# LM5116.net
KiCad netlist of a schematic drawn in EAGLE
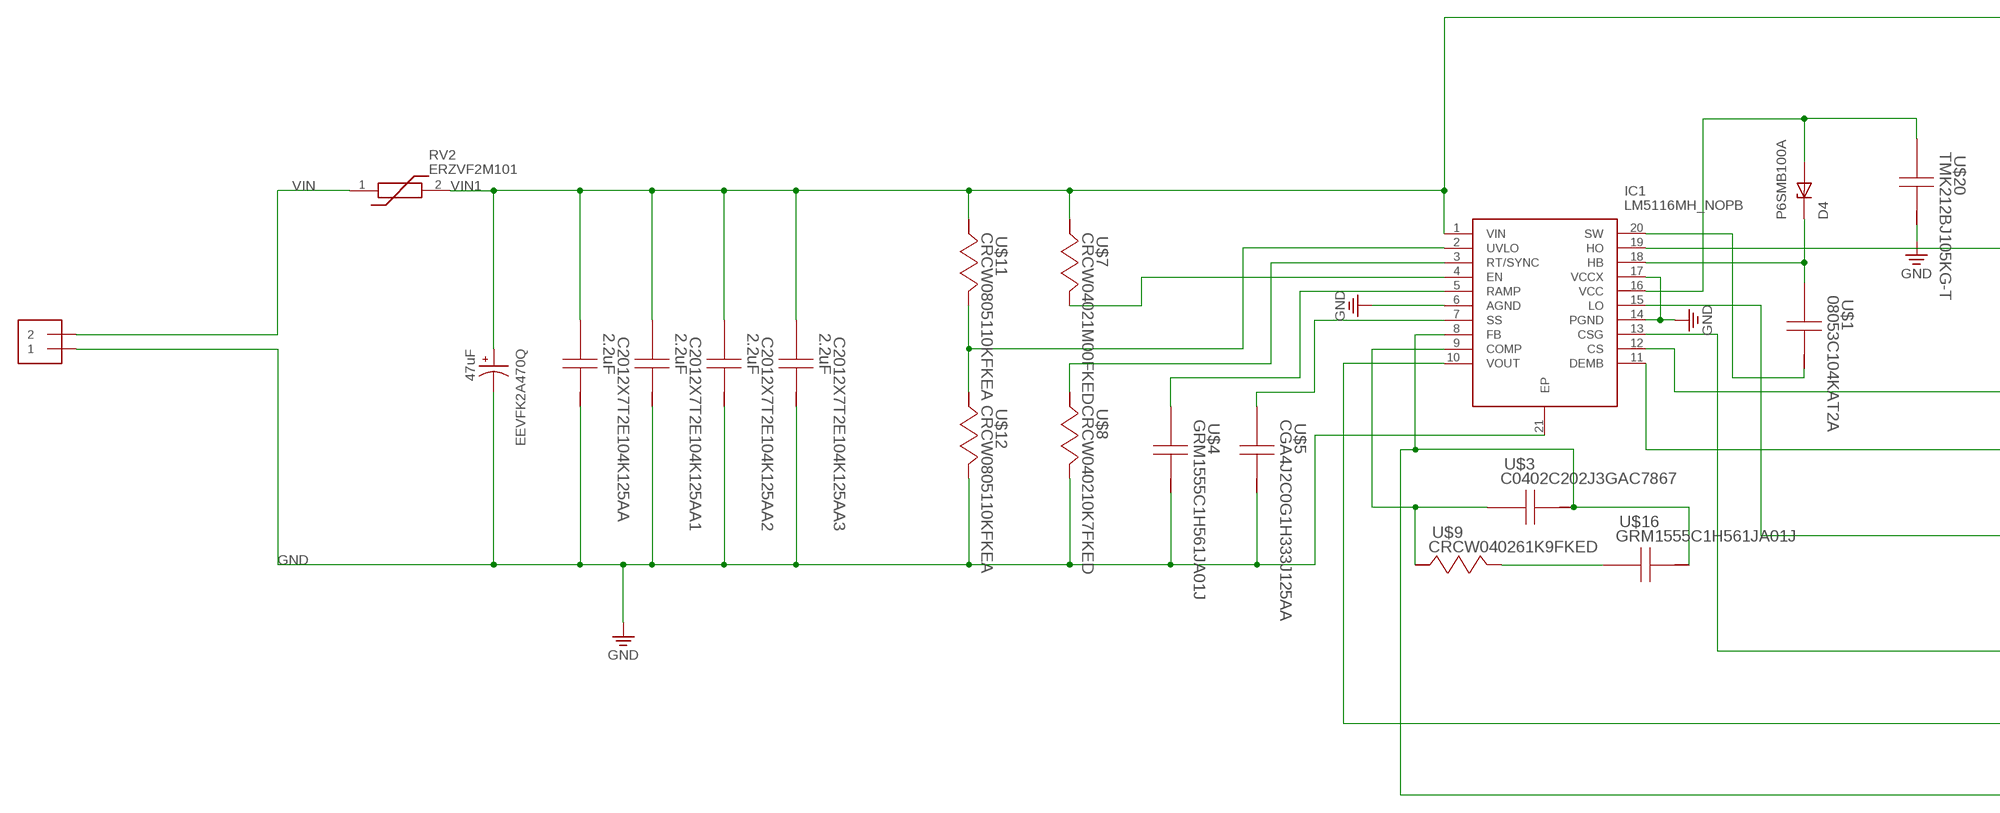
[diagram p0: schematic, sheet 1, part 1 of 2]
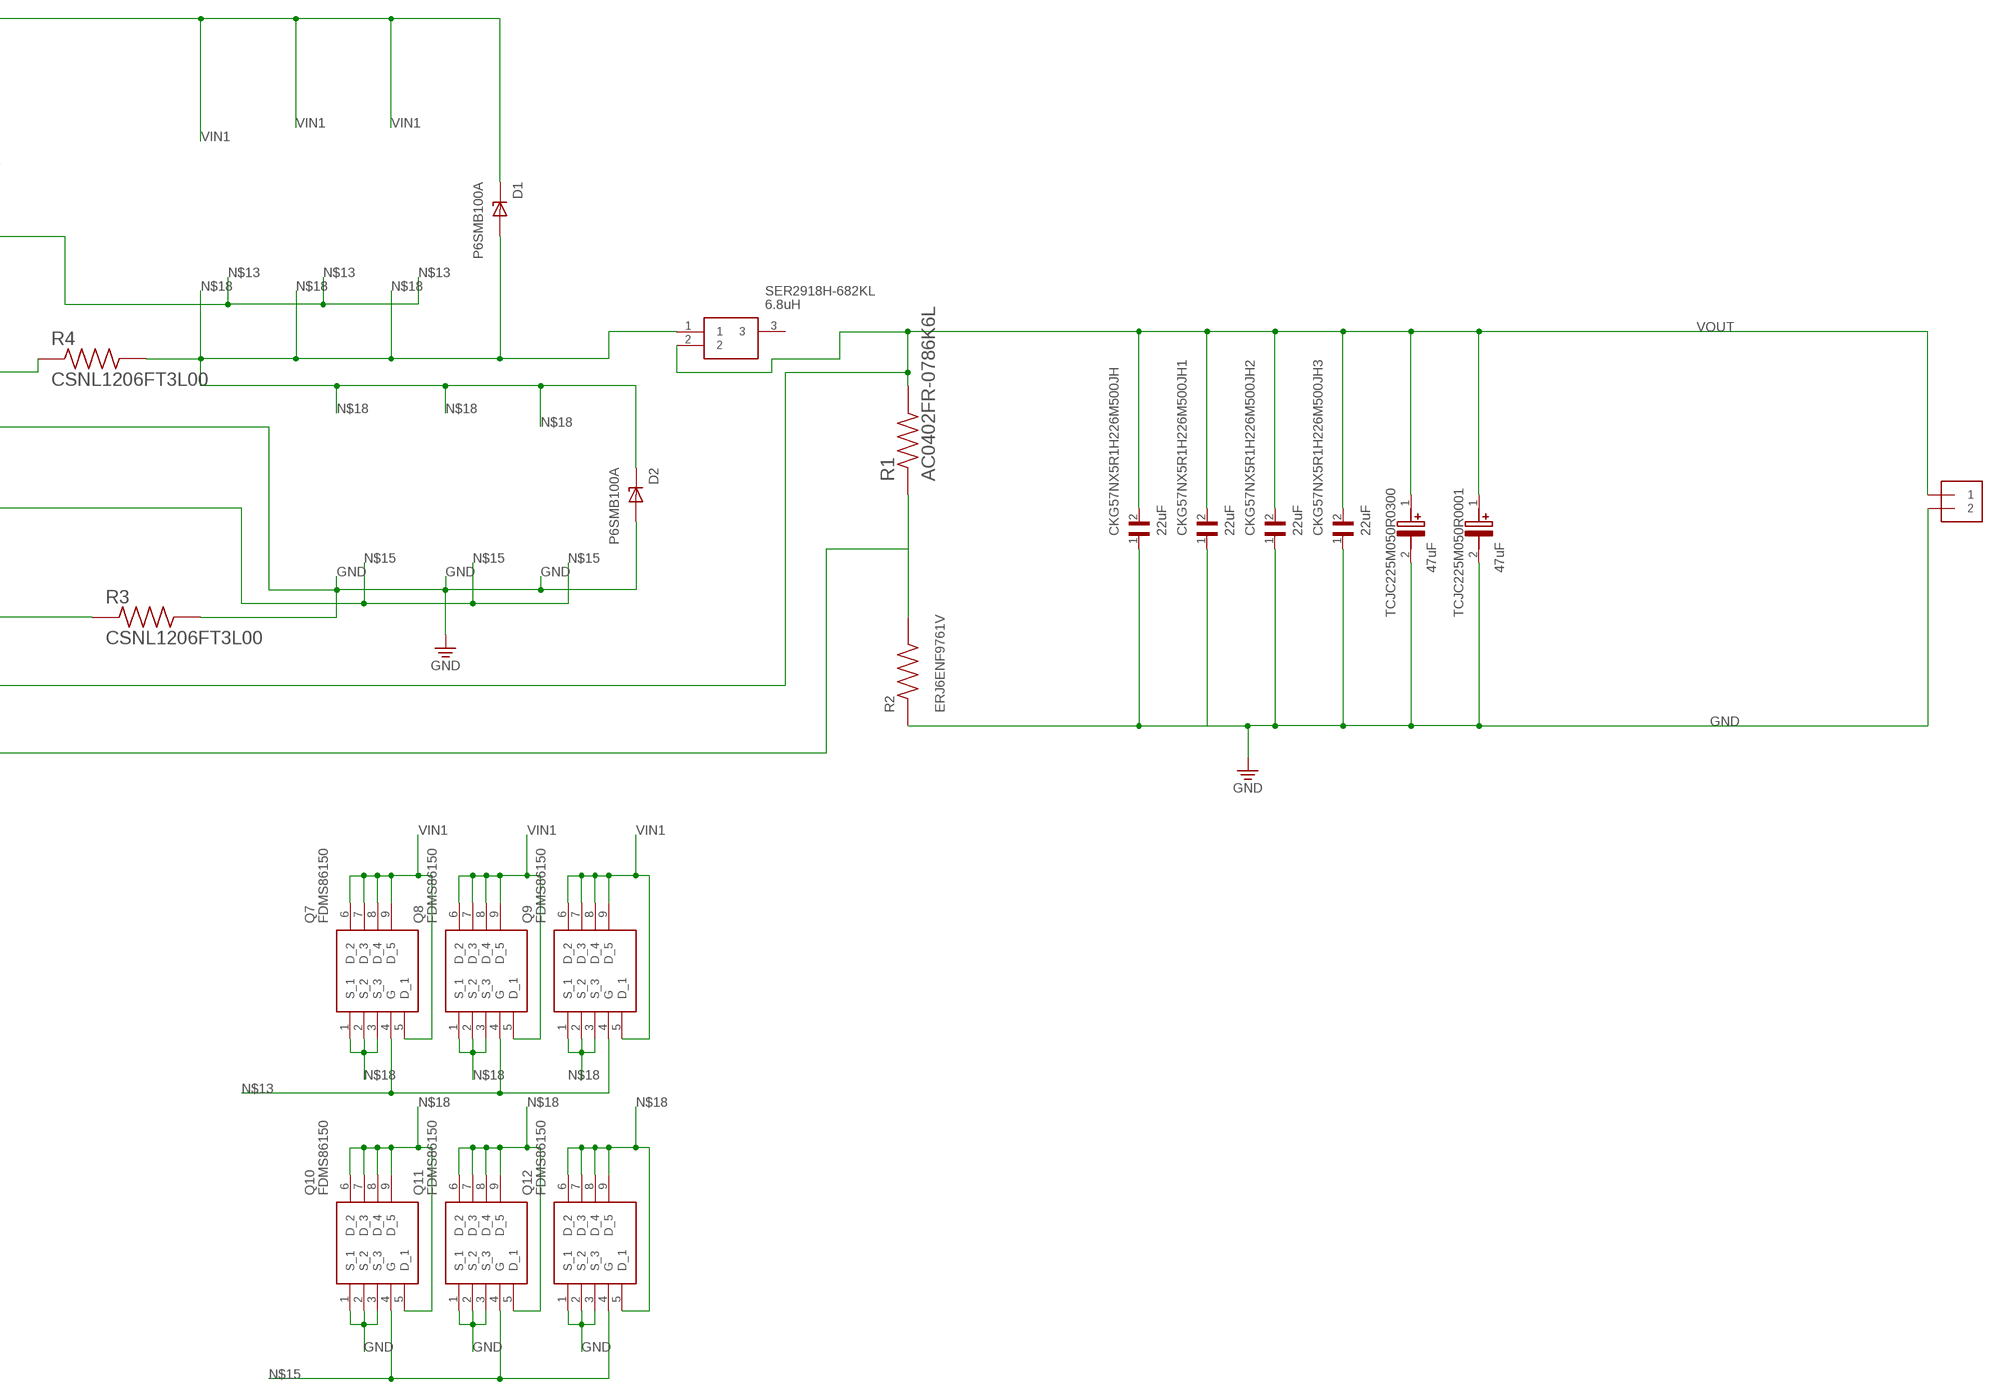
[diagram p1: schematic, sheet 1, part 2 of 2]

(export (version "E")
  (design (tool "Eeschema 10.0.6"))
  (components
    (comp (ref "C2012X7T2E104K125AA")
      (value "2.2uF")
      (footprint "eagle-import:0805")
      (fields (field (name "MANUFACTURER_PART_NUMBER") "C2012X7T2E104K125AA"))
      (libsource (lib "eagle-import") (part "C2012X7T2E104K125AA"))
    )
    (comp (ref "C2012X7T2E104K125AA1")
      (value "2.2uF")
      (footprint "eagle-import:0805")
      (fields (field (name "MANUFACTURER_PART_NUMBER") "C2012X7T2E104K125AA"))
      (libsource (lib "eagle-import") (part "C2012X7T2E104K125AA"))
    )
    (comp (ref "C2012X7T2E104K125AA2")
      (value "2.2uF")
      (footprint "eagle-import:0805")
      (fields (field (name "MANUFACTURER_PART_NUMBER") "C2012X7T2E104K125AA"))
      (libsource (lib "eagle-import") (part "C2012X7T2E104K125AA"))
    )
    (comp (ref "C2012X7T2E104K125AA3")
      (value "2.2uF")
      (footprint "eagle-import:0805")
      (fields (field (name "MANUFACTURER_PART_NUMBER") "C2012X7T2E104K125AA"))
      (libsource (lib "eagle-import") (part "C2012X7T2E104K125AA"))
    )
    (comp (ref "CKG57NX5R1H226M500JH")
      (value "22uF")
      (footprint "eagle-import:CAPC6050X550N")
      (fields (field (name "MF") "TDK Electronics") (field (name "MP") "CKG57NX5R1H226M500JH"))
      (libsource (lib "eagle-import") (part "CKG57NX5R1H226M500JH"))
    )
    (comp (ref "CKG57NX5R1H226M500JH1")
      (value "22uF")
      (footprint "eagle-import:CAPC6050X550N")
      (fields (field (name "MF") "TDK Electronics") (field (name "MP") "CKG57NX5R1H226M500JH"))
      (libsource (lib "eagle-import") (part "CKG57NX5R1H226M500JH"))
    )
    (comp (ref "CKG57NX5R1H226M500JH2")
      (value "22uF")
      (footprint "eagle-import:CAPC6050X550N")
      (fields (field (name "MF") "TDK Electronics") (field (name "MP") "CKG57NX5R1H226M500JH"))
      (libsource (lib "eagle-import") (part "CKG57NX5R1H226M500JH"))
    )
    (comp (ref "CKG57NX5R1H226M500JH3")
      (value "22uF")
      (footprint "eagle-import:CAPC6050X550N")
      (fields (field (name "MF") "TDK Electronics") (field (name "MP") "CKG57NX5R1H226M500JH"))
      (libsource (lib "eagle-import") (part "CKG57NX5R1H226M500JH"))
    )
    (comp (ref "D1")
      (value "P6SMB100A")
      (footprint "eagle-import:DIOM4336X265N")
      (fields
        (field (name "DIGI-KEY_PART_NUMBER") "1801-P6SMB100ATR-ND")
        (field (name "MF") "Taiwan Semiconductor")
      )
      (libsource (lib "eagle-import") (part "P6SMB100A"))
    )
    (comp (ref "D2")
      (value "P6SMB100A")
      (footprint "eagle-import:DIOM4336X265N")
      (fields
        (field (name "DIGI-KEY_PART_NUMBER") "1801-P6SMB100ATR-ND")
        (field (name "MF") "Taiwan Semiconductor")
      )
      (libsource (lib "eagle-import") (part "P6SMB100A"))
    )
    (comp (ref "D4")
      (value "P6SMB100A")
      (footprint "eagle-import:DIOM4336X265N")
      (fields
        (field (name "DIGI-KEY_PART_NUMBER") "1801-P6SMB100ATR-ND")
        (field (name "MF") "Taiwan Semiconductor")
      )
      (libsource (lib "eagle-import") (part "P6SMB100A"))
    )
    (comp (ref "EEVFK2A470Q")
      (value "47uF")
      (footprint "eagle-import:CAP_EEVFK2A470Q")
      (fields (field (name "MF") "Panasonic") (field (name "MP") "EEV-FK2A470Q"))
      (libsource (lib "eagle-import") (part "EEVFK2A470Q"))
    )
    (comp (ref "IC1")
      (value "LM5116MH_NOPB")
      (footprint "eagle-import:SOP65P640X110-21N")
      (fields
        (field (name "ARROW_PART_NUMBER") "LM5116MH/NOPB")
        (field (name "MOUSER_PART_NUMBER") "926-LM5116MH/NOPB")
      )
      (libsource (lib "eagle-import") (part "LM5116MH_NOPB"))
    )
    (comp (ref "J1")
      (value "1X2-3.5MM")
      (footprint "eagle-import:1X2-3.5MM")
      (libsource (lib "eagle-import") (part "1X2-3.5MM"))
    )
    (comp (ref "J2")
      (value "1X2-3.5MM")
      (footprint "eagle-import:1X2-3.5MM")
      (libsource (lib "eagle-import") (part "1X2-3.5MM"))
    )
    (comp (ref "Q7")
      (value "FDMS86150")
      (footprint "eagle-import:FDMS86150")
      (fields (field (name "MOUSER_PART_NUMBER") "512-FDMS86150"))
      (libsource (lib "eagle-import") (part "FDMS86150"))
    )
    (comp (ref "Q8")
      (value "FDMS86150")
      (footprint "eagle-import:FDMS86150")
      (fields (field (name "MOUSER_PART_NUMBER") "512-FDMS86150"))
      (libsource (lib "eagle-import") (part "FDMS86150"))
    )
    (comp (ref "Q9")
      (value "FDMS86150")
      (footprint "eagle-import:FDMS86150")
      (fields (field (name "MOUSER_PART_NUMBER") "512-FDMS86150"))
      (libsource (lib "eagle-import") (part "FDMS86150"))
    )
    (comp (ref "Q10")
      (value "FDMS86150")
      (footprint "eagle-import:FDMS86150")
      (fields (field (name "MOUSER_PART_NUMBER") "512-FDMS86150"))
      (libsource (lib "eagle-import") (part "FDMS86150"))
    )
    (comp (ref "Q11")
      (value "FDMS86150")
      (footprint "eagle-import:FDMS86150")
      (fields (field (name "MOUSER_PART_NUMBER") "512-FDMS86150"))
      (libsource (lib "eagle-import") (part "FDMS86150"))
    )
    (comp (ref "Q12")
      (value "FDMS86150")
      (footprint "eagle-import:FDMS86150")
      (fields (field (name "MOUSER_PART_NUMBER") "512-FDMS86150"))
      (libsource (lib "eagle-import") (part "FDMS86150"))
    )
    (comp (ref "R1")
      (value "AC0402FR-0786K6L")
      (footprint "eagle-import:RESC1005X37N")
      (fields (field (name "DIGI-KEY_PART_NUMBER") "YAG5692TR-ND") (field (name "MF") "Yageo"))
      (libsource (lib "eagle-import") (part "AC0402FR-0786K6L"))
    )
    (comp (ref "R2")
      (value "ERJ6ENF9761V")
      (footprint "eagle-import:RES_ERJ6ENF9761V")
      (fields
        (field (name "DIGI-KEY_PART_NUMBER") "P9.76KCTR-ND")
        (field (name "MF") "Panasonic Electronic")
        (field (name "MP") "ERJ-6ENF9761V")
      )
      (libsource (lib "eagle-import") (part "ERJ6ENF9761V"))
    )
    (comp (ref "R3")
      (value "CSNL1206FT3L00")
      (footprint "eagle-import:RESC3216X90N")
      (fields
        (field (name "DIGI-KEY_PART_NUMBER") "CSNL1206FT3L00TR-ND")
        (field (name "MF") "Stackpole Electronics")
      )
      (libsource (lib "eagle-import") (part "CSNL1206FT3L00"))
    )
    (comp (ref "R4")
      (value "CSNL1206FT3L00")
      (footprint "eagle-import:RESC3216X90N")
      (fields
        (field (name "DIGI-KEY_PART_NUMBER") "CSNL1206FT3L00TR-ND")
        (field (name "MF") "Stackpole Electronics")
      )
      (libsource (lib "eagle-import") (part "CSNL1206FT3L00"))
    )
    (comp (ref "RV2")
      (value "ERZVF2M101")
      (footprint "eagle-import:ERZVF2M101")
      (libsource (lib "eagle-import") (part "ERZVF2M101"))
    )
    (comp (ref "SER2918H-682KL")
      (value "6.8uH")
      (footprint "eagle-import:SER2918H333KL")
      (fields
        (field (name "MANUFACTURER_PART_NUMBER") "SER2918H-682KL")
        (field (name "MOUSER_PART_NUMBER") "994-SER2918H-682KL")
      )
      (libsource (lib "eagle-import") (part "SER2918H-682KL"))
    )
    (comp (ref "TCJC225M050R0001")
      (value "47uF")
      (footprint "eagle-import:CAPPM6032X280N")
      (fields (field (name "MANUFACTURER_PART_NUMBER") "TCJC225M050R0300"))
      (libsource (lib "eagle-import") (part "TCJC225M050R0300"))
    )
    (comp (ref "TCJC225M050R0300")
      (value "47uF")
      (footprint "eagle-import:CAPPM6032X280N")
      (fields (field (name "MANUFACTURER_PART_NUMBER") "TCJC225M050R0300"))
      (libsource (lib "eagle-import") (part "TCJC225M050R0300"))
    )
    (comp (ref "U$1")
      (value "08053C104KAT2A")
      (footprint "eagle-import:0805")
      (libsource (lib "eagle-import") (part "08053C104KAT2A"))
    )
    (comp (ref "U$3")
      (value "C0402C202J3GAC7867")
      (footprint "eagle-import:0402")
      (libsource (lib "eagle-import") (part "C0402C202J3GAC7867"))
    )
    (comp (ref "U$4")
      (value "GRM1555C1H561JA01J")
      (footprint "eagle-import:0402")
      (libsource (lib "eagle-import") (part "GRM1555C1H561JA01J"))
    )
    (comp (ref "U$5")
      (value "CGA4J2C0G1H333J125AA")
      (footprint "eagle-import:0805")
      (libsource (lib "eagle-import") (part "CGA4J2C0G1H333J125AA"))
    )
    (comp (ref "U$7")
      (value "CRCW04021M00FKED")
      (footprint "eagle-import:0402")
      (libsource (lib "eagle-import") (part "CRCW04021M00FKED"))
    )
    (comp (ref "U$8")
      (value "CRCW040210K7FKED")
      (footprint "eagle-import:0402")
      (libsource (lib "eagle-import") (part "CRCW040210K7FKED"))
    )
    (comp (ref "U$9")
      (value "CRCW040261K9FKED")
      (footprint "eagle-import:0402")
      (fields (field (name "MANUFACTURER_PART_NUMBER") "CRCW040216K9FKED"))
      (libsource (lib "eagle-import") (part "CRCW040216K9FKED"))
    )
    (comp (ref "U$11")
      (value "CRCW0805110KFKEA")
      (footprint "eagle-import:0805")
      (libsource (lib "eagle-import") (part "CRCW0805110KFKEA"))
    )
    (comp (ref "U$12")
      (value "CRCW0805110KFKEA")
      (footprint "eagle-import:0805")
      (libsource (lib "eagle-import") (part "CRCW0805110KFKEA"))
    )
    (comp (ref "U$16")
      (value "GRM1555C1H561JA01J")
      (footprint "eagle-import:0402")
      (libsource (lib "eagle-import") (part "GRM1555C1H561JA01J"))
    )
    (comp (ref "U$20")
      (value "TMK212BJ105KG-T")
      (footprint "eagle-import:0805")
      (fields (field (name "MANUFACTURER_PART_NUMBER") "TMK212BJ105KGT"))
      (libsource (lib "eagle-import") (part "TMK212BJ105KG-T"))
    )
  )
  (nets
    (net (code "1") (name "/N$13") (class "Default")
      (node (ref "IC1") (pin "19") (pinfunction "HO_19") (pintype "bidirectional"))
      (node (ref "Q7") (pin "4") (pinfunction "G_4") (pintype "bidirectional"))
      (node (ref "Q8") (pin "4") (pinfunction "G_4") (pintype "bidirectional"))
      (node (ref "Q9") (pin "4") (pinfunction "G_4") (pintype "bidirectional"))
    )
    (net (code "2") (name "/N$15") (class "Default")
      (node (ref "IC1") (pin "15") (pinfunction "LO_15") (pintype "bidirectional"))
      (node (ref "Q10") (pin "4") (pinfunction "G_4") (pintype "bidirectional"))
      (node (ref "Q11") (pin "4") (pinfunction "G_4") (pintype "bidirectional"))
      (node (ref "Q12") (pin "4") (pinfunction "G_4") (pintype "bidirectional"))
    )
    (net (code "3") (name "/N$18") (class "Default")
      (node (ref "D1") (pin "A") (pinfunction "A_A") (pintype "passive"))
      (node (ref "D2") (pin "C") (pinfunction "C_C") (pintype "passive"))
      (node (ref "Q10") (pin "5") (pinfunction "D_1_5") (pintype "bidirectional"))
      (node (ref "Q10") (pin "6") (pinfunction "D_2_6") (pintype "bidirectional"))
      (node (ref "Q10") (pin "7") (pinfunction "D_3_7") (pintype "bidirectional"))
      (node (ref "Q10") (pin "8") (pinfunction "D_4_8") (pintype "bidirectional"))
      (node (ref "Q10") (pin "9") (pinfunction "D_5_9") (pintype "bidirectional"))
      (node (ref "Q11") (pin "5") (pinfunction "D_1_5") (pintype "bidirectional"))
      (node (ref "Q11") (pin "6") (pinfunction "D_2_6") (pintype "bidirectional"))
      (node (ref "Q11") (pin "7") (pinfunction "D_3_7") (pintype "bidirectional"))
      (node (ref "Q11") (pin "8") (pinfunction "D_4_8") (pintype "bidirectional"))
      (node (ref "Q11") (pin "9") (pinfunction "D_5_9") (pintype "bidirectional"))
      (node (ref "Q12") (pin "5") (pinfunction "D_1_5") (pintype "bidirectional"))
      (node (ref "Q12") (pin "6") (pinfunction "D_2_6") (pintype "bidirectional"))
      (node (ref "Q12") (pin "7") (pinfunction "D_3_7") (pintype "bidirectional"))
      (node (ref "Q12") (pin "8") (pinfunction "D_4_8") (pintype "bidirectional"))
      (node (ref "Q12") (pin "9") (pinfunction "D_5_9") (pintype "bidirectional"))
      (node (ref "Q7") (pin "1") (pinfunction "S_1_1") (pintype "bidirectional"))
      (node (ref "Q7") (pin "2") (pinfunction "S_2_2") (pintype "bidirectional"))
      (node (ref "Q7") (pin "3") (pinfunction "S_3_3") (pintype "bidirectional"))
      (node (ref "Q8") (pin "1") (pinfunction "S_1_1") (pintype "bidirectional"))
      (node (ref "Q8") (pin "2") (pinfunction "S_2_2") (pintype "bidirectional"))
      (node (ref "Q8") (pin "3") (pinfunction "S_3_3") (pintype "bidirectional"))
      (node (ref "Q9") (pin "1") (pinfunction "S_1_1") (pintype "bidirectional"))
      (node (ref "Q9") (pin "2") (pinfunction "S_2_2") (pintype "bidirectional"))
      (node (ref "Q9") (pin "3") (pinfunction "S_3_3") (pintype "bidirectional"))
      (node (ref "R4") (pin "2") (pinfunction "2_2") (pintype "passive"))
      (node (ref "SER2918H-682KL") (pin "1") (pinfunction "1_1") (pintype "bidirectional"))
    )
    (net (code "4") (name "/VIN") (class "Default")
      (node (ref "J1") (pin "2") (pinfunction "2_2") (pintype "passive"))
      (node (ref "RV2") (pin "1") (pinfunction "1_1") (pintype "bidirectional"))
    )
    (net (code "5") (name "/VIN1") (class "Default")
      (node (ref "C2012X7T2E104K125AA") (pin "2") (pinfunction "2_2") (pintype "passive"))
      (node (ref "C2012X7T2E104K125AA1") (pin "2") (pinfunction "2_2") (pintype "passive"))
      (node (ref "C2012X7T2E104K125AA2") (pin "2") (pinfunction "2_2") (pintype "passive"))
      (node (ref "C2012X7T2E104K125AA3") (pin "2") (pinfunction "2_2") (pintype "passive"))
      (node (ref "D1") (pin "C") (pinfunction "C_C") (pintype "passive"))
      (node (ref "EEVFK2A470Q") (pin "1") (pinfunction "1_1") (pintype "passive"))
      (node (ref "IC1") (pin "1") (pinfunction "VIN_1") (pintype "bidirectional"))
      (node (ref "Q7") (pin "5") (pinfunction "D_1_5") (pintype "bidirectional"))
      (node (ref "Q7") (pin "6") (pinfunction "D_2_6") (pintype "bidirectional"))
      (node (ref "Q7") (pin "7") (pinfunction "D_3_7") (pintype "bidirectional"))
      (node (ref "Q7") (pin "8") (pinfunction "D_4_8") (pintype "bidirectional"))
      (node (ref "Q7") (pin "9") (pinfunction "D_5_9") (pintype "bidirectional"))
      (node (ref "Q8") (pin "5") (pinfunction "D_1_5") (pintype "bidirectional"))
      (node (ref "Q8") (pin "6") (pinfunction "D_2_6") (pintype "bidirectional"))
      (node (ref "Q8") (pin "7") (pinfunction "D_3_7") (pintype "bidirectional"))
      (node (ref "Q8") (pin "8") (pinfunction "D_4_8") (pintype "bidirectional"))
      (node (ref "Q8") (pin "9") (pinfunction "D_5_9") (pintype "bidirectional"))
      (node (ref "Q9") (pin "5") (pinfunction "D_1_5") (pintype "bidirectional"))
      (node (ref "Q9") (pin "6") (pinfunction "D_2_6") (pintype "bidirectional"))
      (node (ref "Q9") (pin "7") (pinfunction "D_3_7") (pintype "bidirectional"))
      (node (ref "Q9") (pin "8") (pinfunction "D_4_8") (pintype "bidirectional"))
      (node (ref "Q9") (pin "9") (pinfunction "D_5_9") (pintype "bidirectional"))
      (node (ref "RV2") (pin "2") (pinfunction "2_2") (pintype "bidirectional"))
      (node (ref "U$11") (pin "2") (pinfunction "2_2") (pintype "passive"))
      (node (ref "U$7") (pin "2") (pinfunction "2_2") (pintype "passive"))
    )
    (net (code "6") (name "/VOUT") (class "Default")
      (node (ref "CKG57NX5R1H226M500JH") (pin "2") (pinfunction "2_2") (pintype "passive"))
      (node (ref "CKG57NX5R1H226M500JH1") (pin "2") (pinfunction "2_2") (pintype "passive"))
      (node (ref "CKG57NX5R1H226M500JH2") (pin "2") (pinfunction "2_2") (pintype "passive"))
      (node (ref "CKG57NX5R1H226M500JH3") (pin "2") (pinfunction "2_2") (pintype "passive"))
      (node (ref "IC1") (pin "10") (pinfunction "VOUT_10") (pintype "bidirectional"))
      (node (ref "J2") (pin "1") (pinfunction "1_1") (pintype "passive"))
      (node (ref "R1") (pin "2") (pinfunction "2_2") (pintype "passive"))
      (node (ref "SER2918H-682KL") (pin "2") (pinfunction "2_2") (pintype "bidirectional"))
      (node (ref "TCJC225M050R0001") (pin "1") (pinfunction "+_1") (pintype "bidirectional"))
      (node (ref "TCJC225M050R0300") (pin "1") (pinfunction "+_1") (pintype "bidirectional"))
    )
    (net (code "7") (name "GND") (class "Default")
      (node (ref "C2012X7T2E104K125AA") (pin "1") (pinfunction "1_1") (pintype "passive"))
      (node (ref "C2012X7T2E104K125AA1") (pin "1") (pinfunction "1_1") (pintype "passive"))
      (node (ref "C2012X7T2E104K125AA2") (pin "1") (pinfunction "1_1") (pintype "passive"))
      (node (ref "C2012X7T2E104K125AA3") (pin "1") (pinfunction "1_1") (pintype "passive"))
      (node (ref "CKG57NX5R1H226M500JH") (pin "1") (pinfunction "1_1") (pintype "passive"))
      (node (ref "CKG57NX5R1H226M500JH1") (pin "1") (pinfunction "1_1") (pintype "passive"))
      (node (ref "CKG57NX5R1H226M500JH2") (pin "1") (pinfunction "1_1") (pintype "passive"))
      (node (ref "CKG57NX5R1H226M500JH3") (pin "1") (pinfunction "1_1") (pintype "passive"))
      (node (ref "D2") (pin "A") (pinfunction "A_A") (pintype "passive"))
      (node (ref "EEVFK2A470Q") (pin "2") (pinfunction "2_2") (pintype "passive"))
      (node (ref "IC1") (pin "11") (pinfunction "DEMB_11") (pintype "bidirectional"))
      (node (ref "IC1") (pin "14") (pinfunction "PGND_14") (pintype "bidirectional"))
      (node (ref "IC1") (pin "17") (pinfunction "VCCX_17") (pintype "bidirectional"))
      (node (ref "IC1") (pin "21") (pinfunction "EP_21") (pintype "bidirectional"))
      (node (ref "IC1") (pin "6") (pinfunction "AGND_6") (pintype "bidirectional"))
      (node (ref "J1") (pin "1") (pinfunction "1_1") (pintype "passive"))
      (node (ref "J2") (pin "2") (pinfunction "2_2") (pintype "passive"))
      (node (ref "Q10") (pin "1") (pinfunction "S_1_1") (pintype "bidirectional"))
      (node (ref "Q10") (pin "2") (pinfunction "S_2_2") (pintype "bidirectional"))
      (node (ref "Q10") (pin "3") (pinfunction "S_3_3") (pintype "bidirectional"))
      (node (ref "Q11") (pin "1") (pinfunction "S_1_1") (pintype "bidirectional"))
      (node (ref "Q11") (pin "2") (pinfunction "S_2_2") (pintype "bidirectional"))
      (node (ref "Q11") (pin "3") (pinfunction "S_3_3") (pintype "bidirectional"))
      (node (ref "Q12") (pin "1") (pinfunction "S_1_1") (pintype "bidirectional"))
      (node (ref "Q12") (pin "2") (pinfunction "S_2_2") (pintype "bidirectional"))
      (node (ref "Q12") (pin "3") (pinfunction "S_3_3") (pintype "bidirectional"))
      (node (ref "R2") (pin "1") (pinfunction "1_1") (pintype "passive"))
      (node (ref "R3") (pin "2") (pinfunction "2_2") (pintype "passive"))
      (node (ref "TCJC225M050R0001") (pin "2") (pinfunction "-_2") (pintype "bidirectional"))
      (node (ref "TCJC225M050R0300") (pin "2") (pinfunction "-_2") (pintype "bidirectional"))
      (node (ref "U$12") (pin "1") (pinfunction "1_1") (pintype "passive"))
      (node (ref "U$20") (pin "1") (pinfunction "1_1") (pintype "passive"))
      (node (ref "U$4") (pin "1") (pinfunction "1_1") (pintype "passive"))
      (node (ref "U$5") (pin "1") (pinfunction "1_1") (pintype "passive"))
      (node (ref "U$8") (pin "1") (pinfunction "1_1") (pintype "passive"))
    )
    (net (code "8") (name "Net-(IC1-COMP)") (class "Default")
      (node (ref "IC1") (pin "9") (pinfunction "COMP_9") (pintype "bidirectional"))
      (node (ref "U$3") (pin "2") (pinfunction "2_2") (pintype "passive"))
      (node (ref "U$9") (pin "2") (pinfunction "2_2") (pintype "passive"))
    )
    (net (code "9") (name "Net-(IC1-CS)") (class "Default")
      (node (ref "IC1") (pin "12") (pinfunction "CS_12") (pintype "bidirectional"))
      (node (ref "R4") (pin "1") (pinfunction "1_1") (pintype "passive"))
    )
    (net (code "10") (name "Net-(IC1-CSG)") (class "Default")
      (node (ref "IC1") (pin "13") (pinfunction "CSG_13") (pintype "bidirectional"))
      (node (ref "R3") (pin "1") (pinfunction "1_1") (pintype "passive"))
    )
    (net (code "11") (name "Net-(IC1-EN)") (class "Default")
      (node (ref "IC1") (pin "4") (pinfunction "EN_4") (pintype "bidirectional"))
      (node (ref "U$7") (pin "1") (pinfunction "1_1") (pintype "passive"))
    )
    (net (code "12") (name "Net-(IC1-FB)") (class "Default")
      (node (ref "IC1") (pin "8") (pinfunction "FB_8") (pintype "bidirectional"))
      (node (ref "R1") (pin "1") (pinfunction "1_1") (pintype "passive"))
      (node (ref "R2") (pin "2") (pinfunction "2_2") (pintype "passive"))
      (node (ref "U$16") (pin "1") (pinfunction "1_1") (pintype "passive"))
      (node (ref "U$3") (pin "1") (pinfunction "1_1") (pintype "passive"))
    )
    (net (code "13") (name "Net-(IC1-HB)") (class "Default")
      (node (ref "D4") (pin "C") (pinfunction "C_C") (pintype "passive"))
      (node (ref "IC1") (pin "18") (pinfunction "HB_18") (pintype "bidirectional"))
      (node (ref "U$1") (pin "2") (pinfunction "2_2") (pintype "passive"))
    )
    (net (code "14") (name "Net-(IC1-RAMP)") (class "Default")
      (node (ref "IC1") (pin "5") (pinfunction "RAMP_5") (pintype "bidirectional"))
      (node (ref "U$4") (pin "2") (pinfunction "2_2") (pintype "passive"))
    )
    (net (code "15") (name "Net-(IC1-RT{slash}SYNC)") (class "Default")
      (node (ref "IC1") (pin "3") (pinfunction "RT/SYNC_3") (pintype "bidirectional"))
      (node (ref "U$8") (pin "2") (pinfunction "2_2") (pintype "passive"))
    )
    (net (code "16") (name "Net-(IC1-SS)") (class "Default")
      (node (ref "IC1") (pin "7") (pinfunction "SS_7") (pintype "bidirectional"))
      (node (ref "U$5") (pin "2") (pinfunction "2_2") (pintype "passive"))
    )
    (net (code "17") (name "Net-(IC1-SW)") (class "Default")
      (node (ref "IC1") (pin "20") (pinfunction "SW_20") (pintype "bidirectional"))
      (node (ref "U$1") (pin "1") (pinfunction "1_1") (pintype "passive"))
    )
    (net (code "18") (name "Net-(IC1-UVLO)") (class "Default")
      (node (ref "IC1") (pin "2") (pinfunction "UVLO_2") (pintype "bidirectional"))
      (node (ref "U$11") (pin "1") (pinfunction "1_1") (pintype "passive"))
      (node (ref "U$12") (pin "2") (pinfunction "2_2") (pintype "passive"))
    )
    (net (code "19") (name "Net-(IC1-VCC)") (class "Default")
      (node (ref "D4") (pin "A") (pinfunction "A_A") (pintype "passive"))
      (node (ref "IC1") (pin "16") (pinfunction "VCC_16") (pintype "bidirectional"))
      (node (ref "U$20") (pin "2") (pinfunction "2_2") (pintype "passive"))
    )
    (net (code "20") (name "Net-(U$16-Pad2)") (class "Default")
      (node (ref "U$16") (pin "2") (pinfunction "2_2") (pintype "passive"))
      (node (ref "U$9") (pin "1") (pinfunction "1_1") (pintype "passive"))
    )
    (net (code "21") (name "unconnected-(SER2918H-682KL-Pad3)") (class "Default")
      (node (ref "SER2918H-682KL") (pin "3") (pinfunction "3_3") (pintype "bidirectional"))
    )
  )
)
